# ModulePlatform.net
KiCad netlist of a schematic drawn in EAGLE
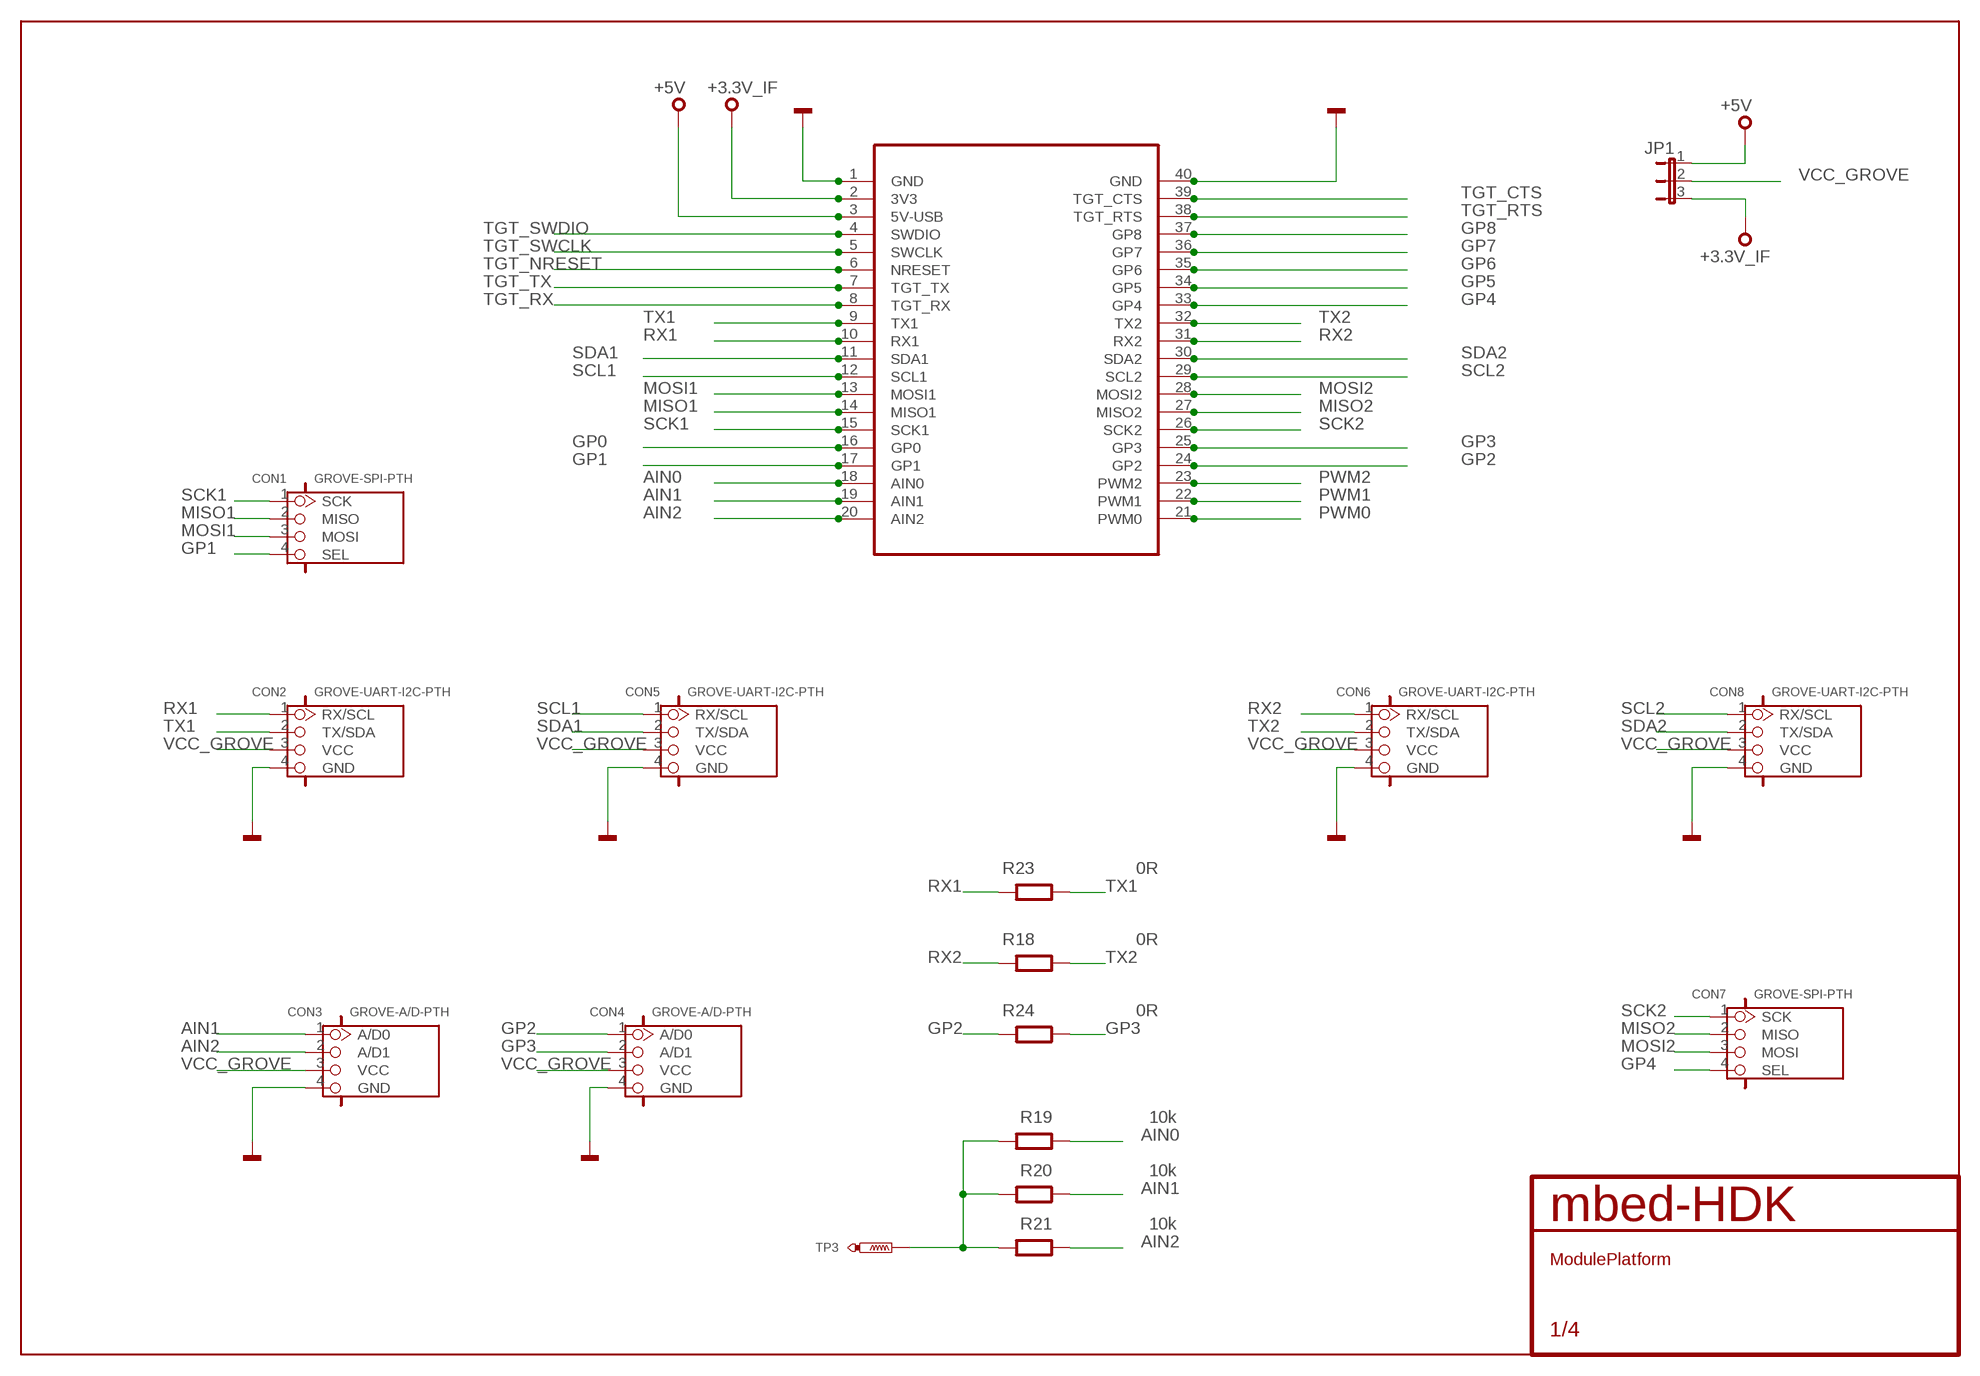
[diagram p0: schematic, sheet 1]
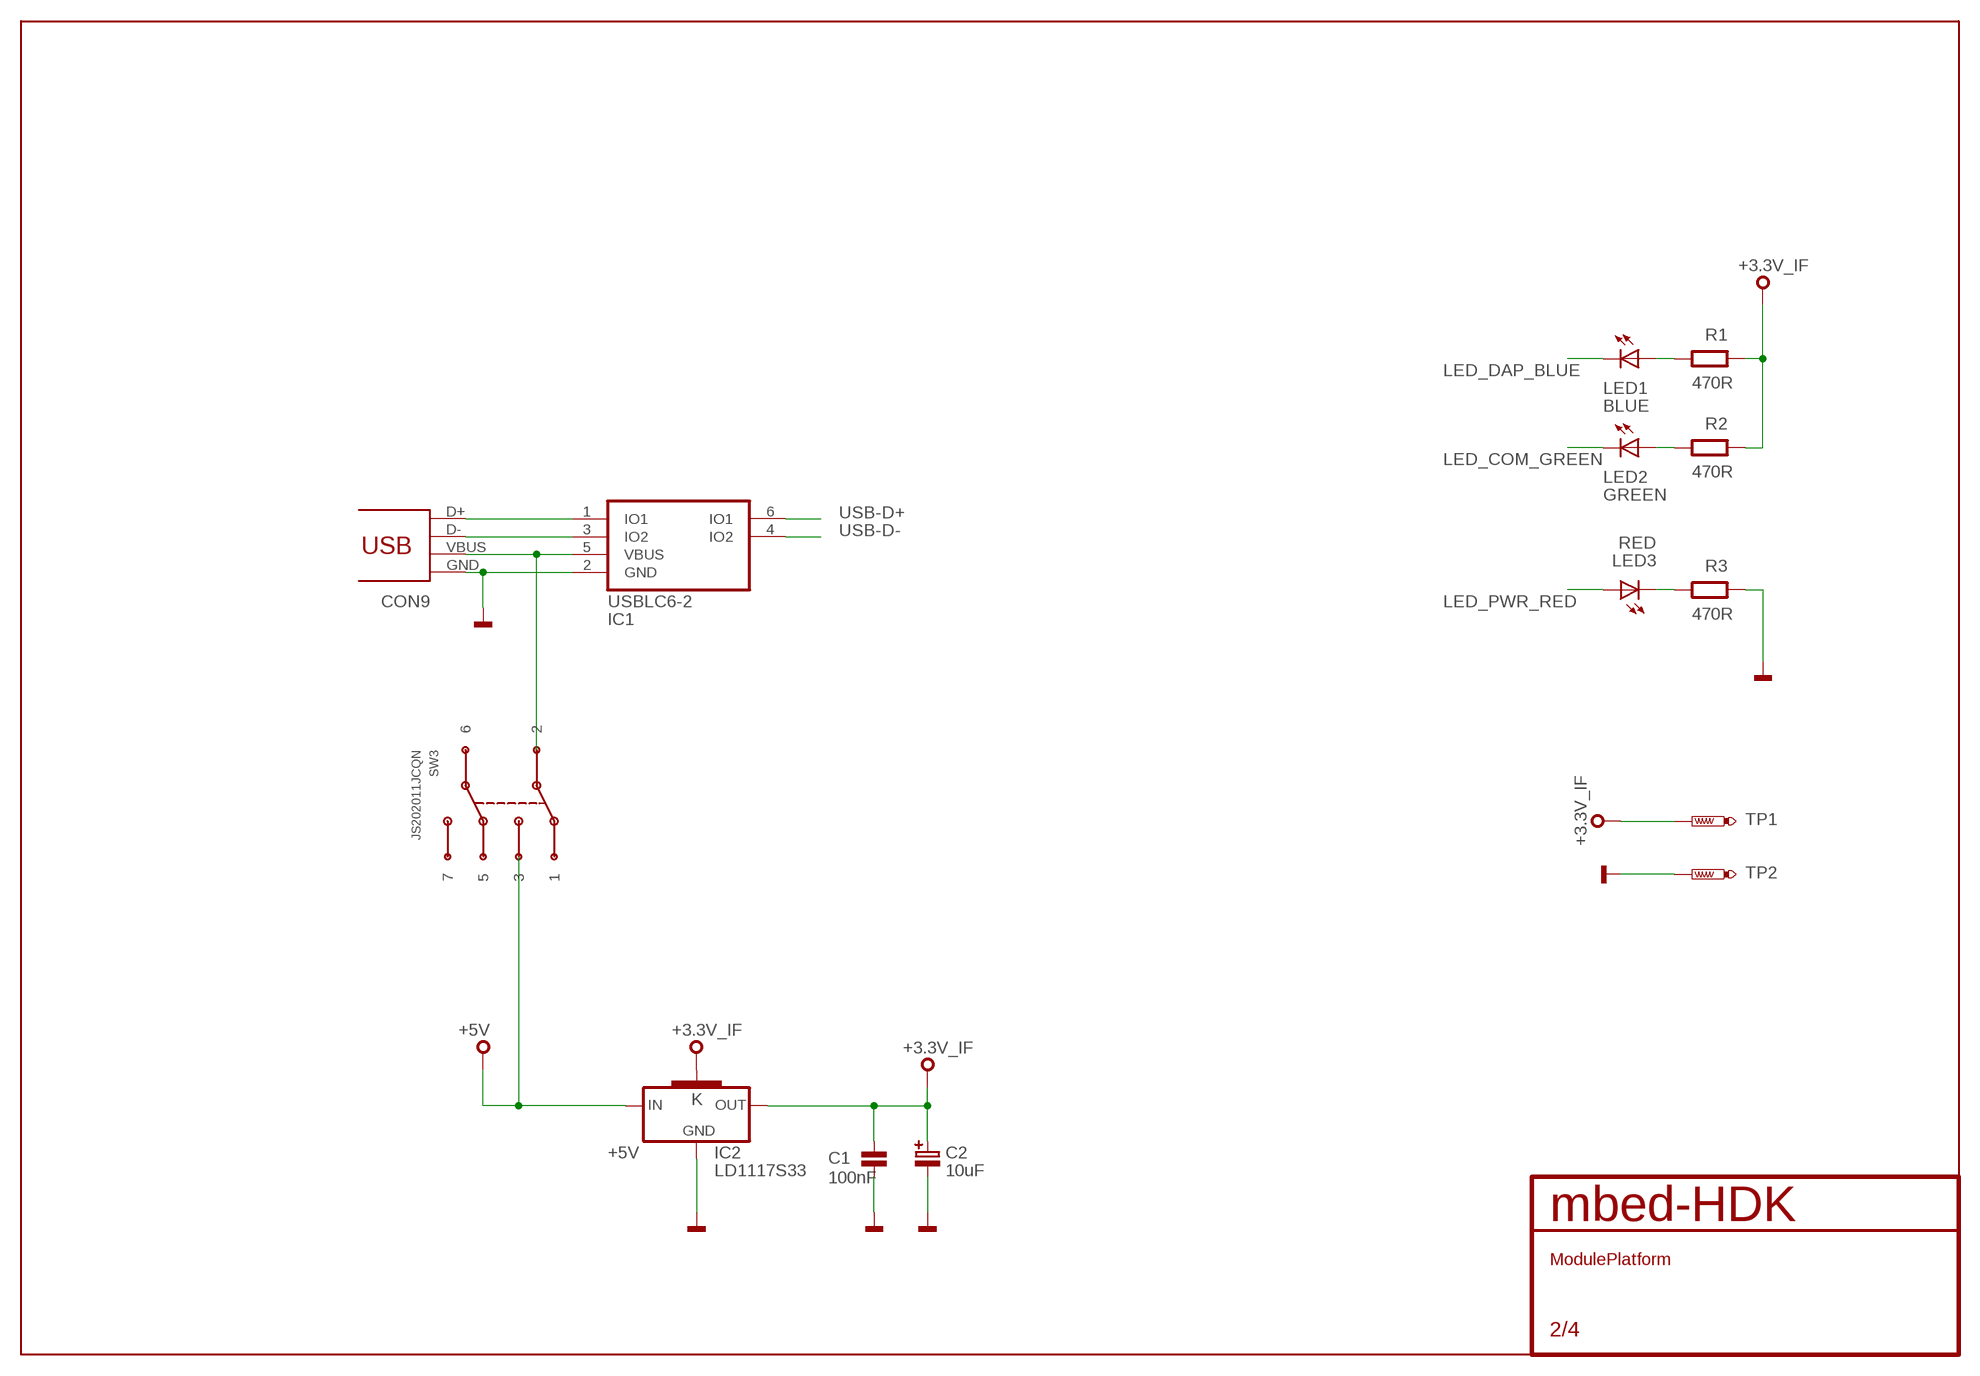
[diagram p1: schematic, sheet 2]
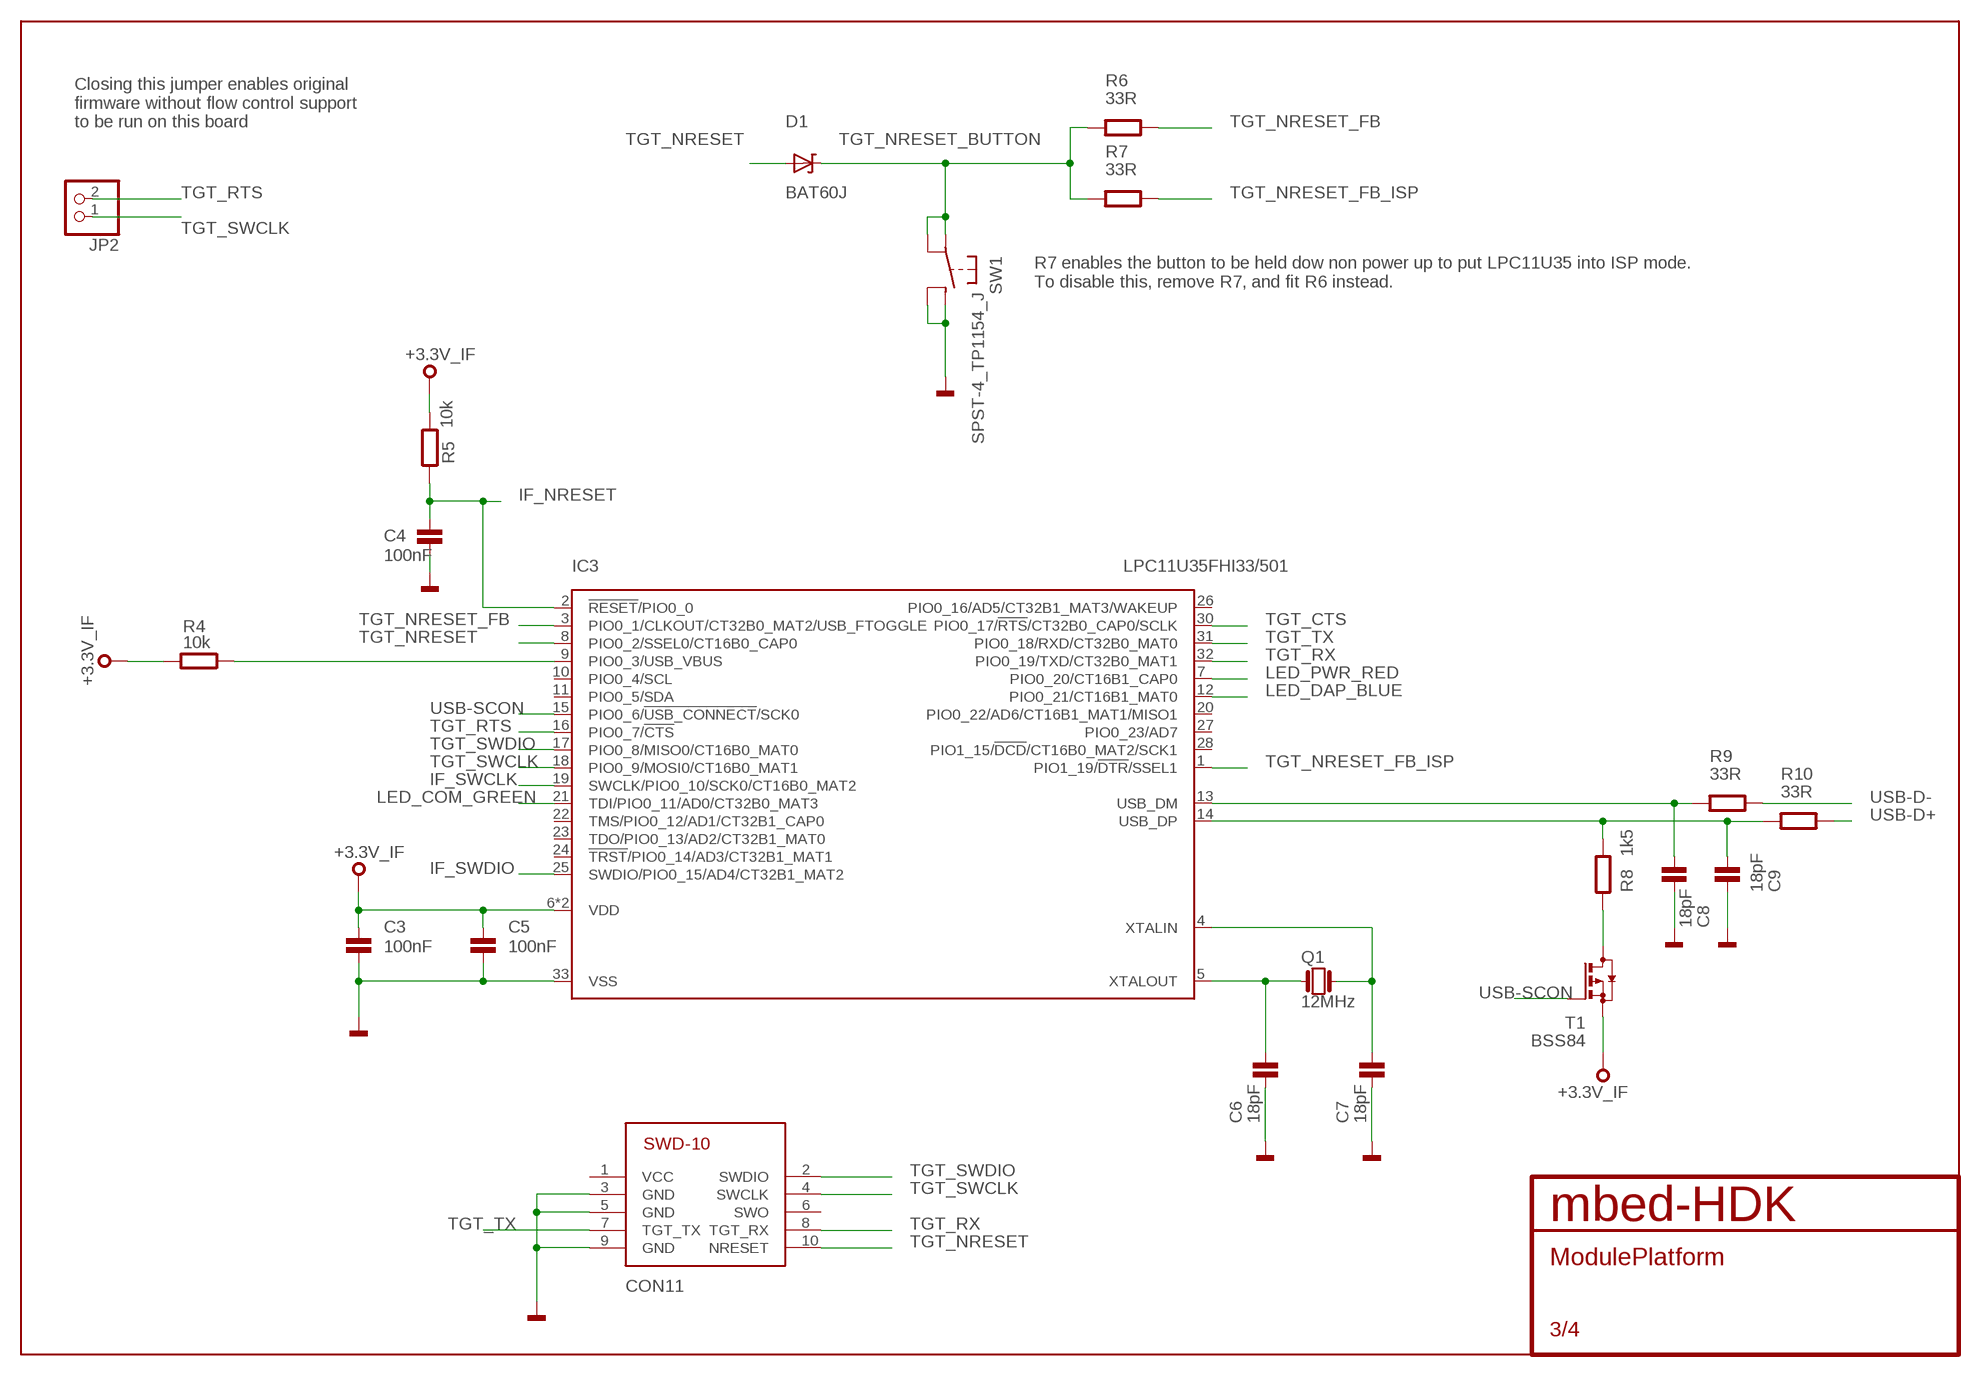
[diagram p2: schematic, sheet 3]
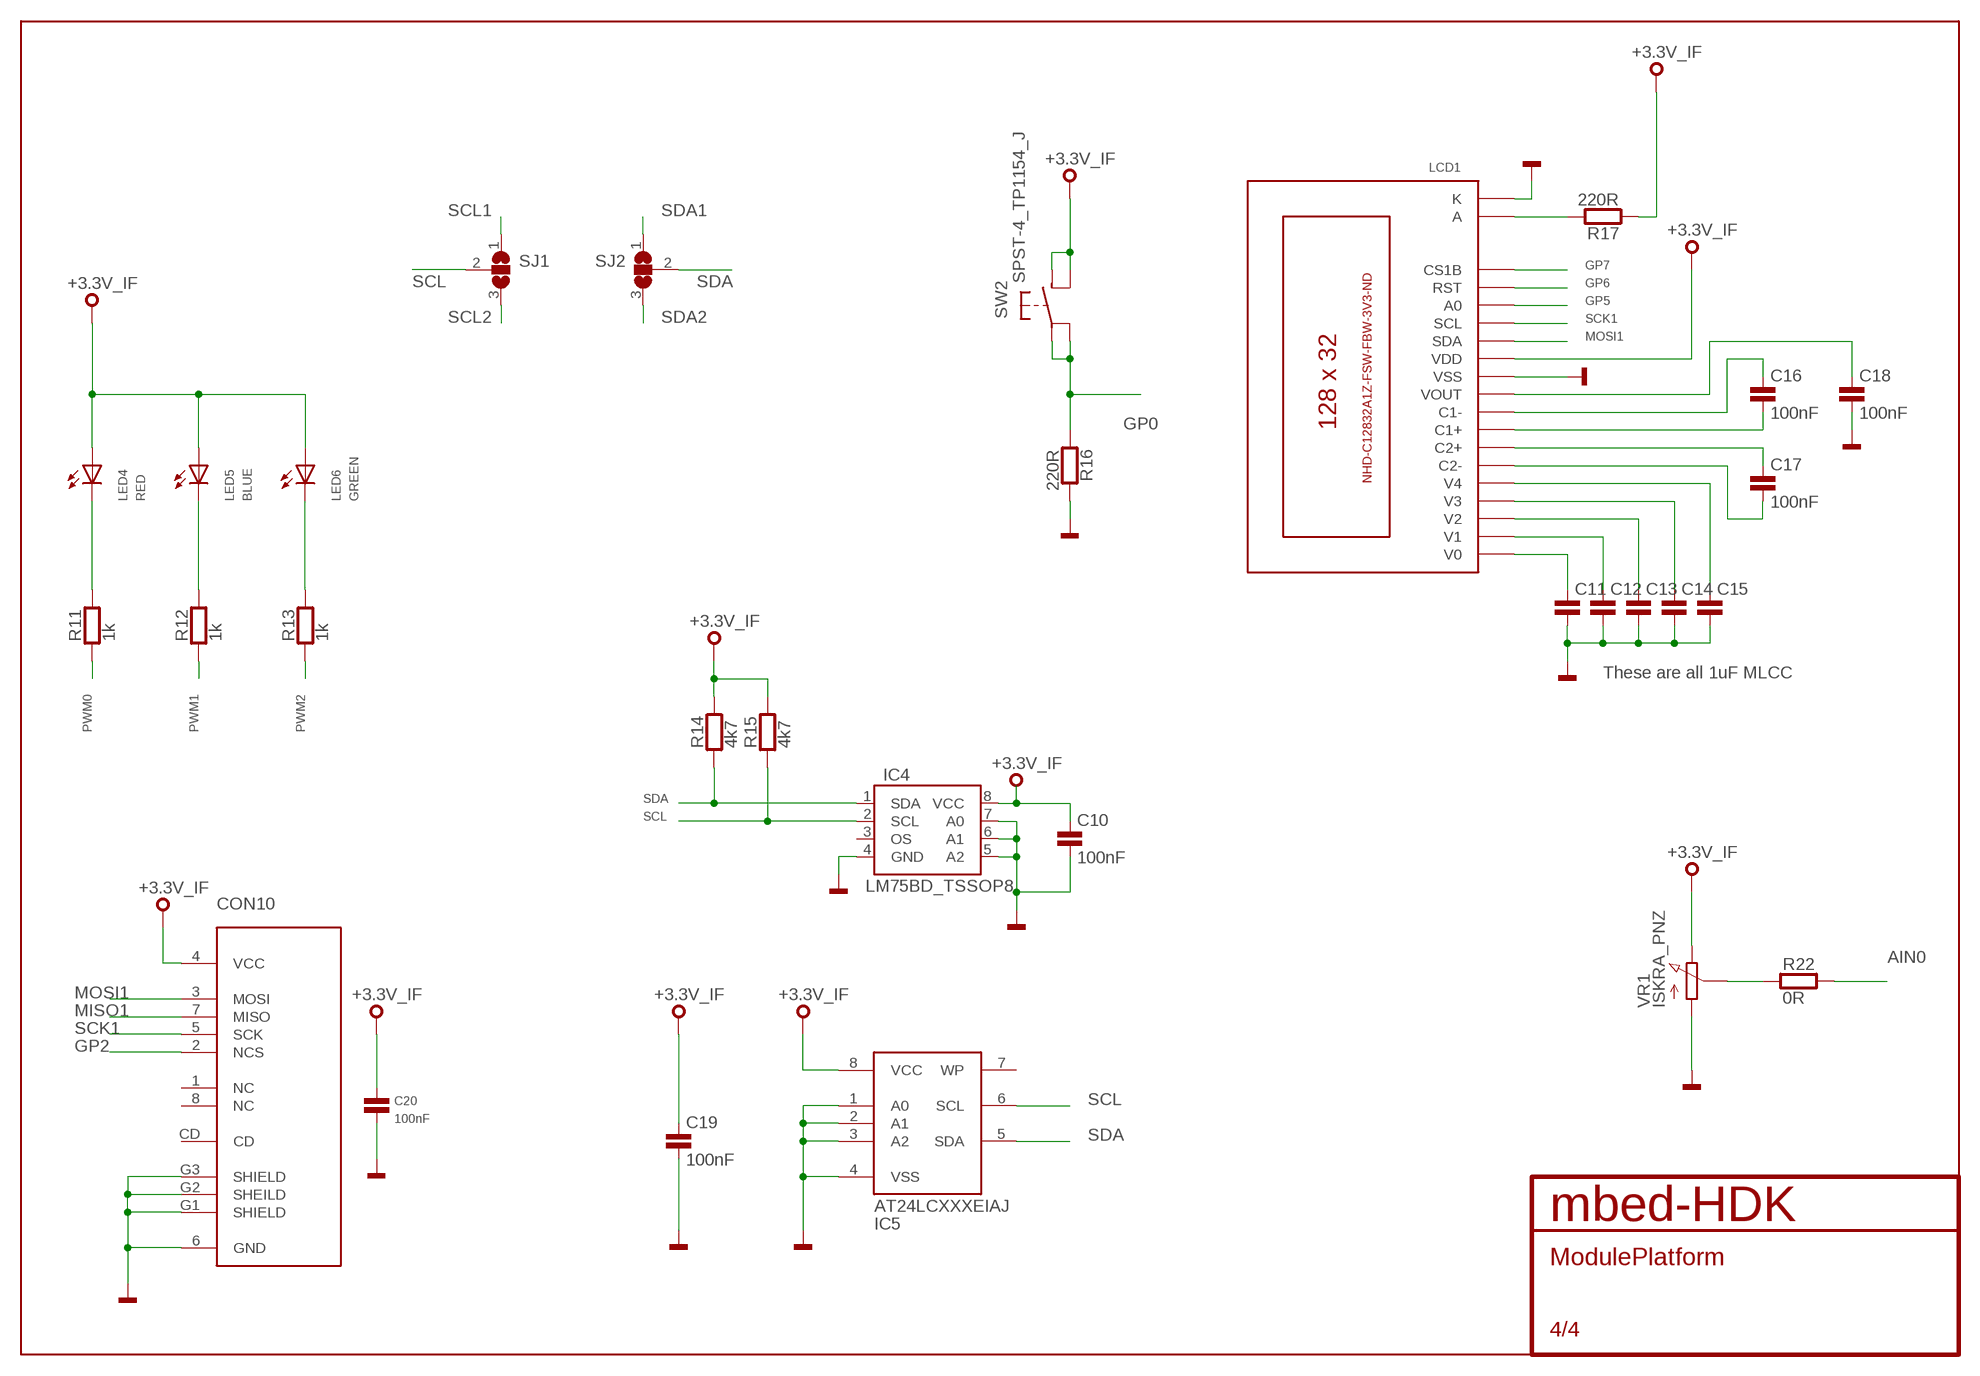
[diagram p3: schematic, sheet 4]

(export (version "E")
  (design (tool "Eeschema 10.0.6"))
  (components
    (comp (ref "CON1")
      (value "GROVE-SPI-PTH")
      (footprint "eagle-import:HW4-2.0")
      (libsource (lib "eagle-import") (part "GROVE-SPI-PTH"))
    )
    (comp (ref "CON2")
      (value "GROVE-UART-I2C-PTH")
      (footprint "eagle-import:HW4-2.0")
      (libsource (lib "eagle-import") (part "GROVE-UART-I2C-PTH"))
    )
    (comp (ref "CON3")
      (value "GROVE-A/D-PTH")
      (footprint "eagle-import:HW4-2.0")
      (libsource (lib "eagle-import") (part "GROVE-A/D-PTH"))
    )
    (comp (ref "CON4")
      (value "GROVE-A/D-PTH")
      (footprint "eagle-import:HW4-2.0")
      (libsource (lib "eagle-import") (part "GROVE-A/D-PTH"))
    )
    (comp (ref "CON5")
      (value "GROVE-UART-I2C-PTH")
      (footprint "eagle-import:HW4-2.0")
      (libsource (lib "eagle-import") (part "GROVE-UART-I2C-PTH"))
    )
    (comp (ref "CON6")
      (value "GROVE-UART-I2C-PTH")
      (footprint "eagle-import:HW4-2.0")
      (libsource (lib "eagle-import") (part "GROVE-UART-I2C-PTH"))
    )
    (comp (ref "CON7")
      (value "GROVE-SPI-PTH")
      (footprint "eagle-import:HW4-2.0")
      (libsource (lib "eagle-import") (part "GROVE-SPI-PTH"))
    )
    (comp (ref "CON8")
      (value "GROVE-UART-I2C-PTH")
      (footprint "eagle-import:HW4-2.0")
      (libsource (lib "eagle-import") (part "GROVE-UART-I2C-PTH"))
    )
    (comp (ref "JP1")
      (value "JP2E")
      (footprint "eagle-import:JP2")
      (libsource (lib "eagle-import") (part "JP2E"))
    )
    (comp (ref "R18")
      (value "0R")
      (footprint "eagle-import:0603@1")
      (libsource (lib "eagle-import") (part "R0603"))
    )
    (comp (ref "R19")
      (value "10k")
      (footprint "eagle-import:0603@1")
      (libsource (lib "eagle-import") (part "R0603"))
    )
    (comp (ref "R20")
      (value "10k")
      (footprint "eagle-import:0603@1")
      (libsource (lib "eagle-import") (part "R0603"))
    )
    (comp (ref "R21")
      (value "10k")
      (footprint "eagle-import:0603@1")
      (libsource (lib "eagle-import") (part "R0603"))
    )
    (comp (ref "R23")
      (value "0R")
      (footprint "eagle-import:0603@1")
      (libsource (lib "eagle-import") (part "R0603"))
    )
    (comp (ref "R24")
      (value "0R")
      (footprint "eagle-import:0603@1")
      (libsource (lib "eagle-import") (part "R0603"))
    )
    (comp (ref "SKT1")
      (value "MODULE_SOCKET")
      (footprint "eagle-import:MODULE_SOCKET")
      (libsource (lib "eagle-import") (part "MODULE_SOCKET"))
    )
    (comp (ref "TP3")
      (value "TEST-POINT-50R-PTH")
      (footprint "eagle-import:TP50-PTH")
      (libsource (lib "eagle-import") (part "TEST-POINT-50R-PTH"))
    )
    (comp (ref "C10")
      (value "100nF")
      (footprint "eagle-import:0603")
      (libsource (lib "eagle-import") (part "mbed-rlcq_C0603"))
    )
    (comp (ref "C11")
      (value "100nF")
      (footprint "eagle-import:0603")
      (libsource (lib "eagle-import") (part "mbed-rlcq_C0603"))
    )
    (comp (ref "C12")
      (value "100nF")
      (footprint "eagle-import:0603")
      (libsource (lib "eagle-import") (part "mbed-rlcq_C0603"))
    )
    (comp (ref "C13")
      (value "100nF")
      (footprint "eagle-import:0603")
      (libsource (lib "eagle-import") (part "mbed-rlcq_C0603"))
    )
    (comp (ref "C14")
      (value "100nF")
      (footprint "eagle-import:0603")
      (libsource (lib "eagle-import") (part "mbed-rlcq_C0603"))
    )
    (comp (ref "C15")
      (value "100nF")
      (footprint "eagle-import:0603")
      (libsource (lib "eagle-import") (part "mbed-rlcq_C0603"))
    )
    (comp (ref "C16")
      (value "100nF")
      (footprint "eagle-import:0603")
      (libsource (lib "eagle-import") (part "mbed-rlcq_C0603"))
    )
    (comp (ref "C17")
      (value "100nF")
      (footprint "eagle-import:0603")
      (libsource (lib "eagle-import") (part "mbed-rlcq_C0603"))
    )
    (comp (ref "C18")
      (value "100nF")
      (footprint "eagle-import:0603")
      (libsource (lib "eagle-import") (part "mbed-rlcq_C0603"))
    )
    (comp (ref "C19")
      (value "100nF")
      (footprint "eagle-import:0603")
      (libsource (lib "eagle-import") (part "mbed-rlcq_C0603"))
    )
    (comp (ref "C20")
      (value "100nF")
      (footprint "eagle-import:0603")
      (libsource (lib "eagle-import") (part "C0603"))
    )
    (comp (ref "CON10")
      (value "MICRO-SD")
      (footprint "eagle-import:AMPHENOL-101-00660-68-6")
      (libsource (lib "eagle-import") (part "MICRO-SD"))
    )
    (comp (ref "IC4")
      (value "LM75BD_TSSOP8")
      (footprint "eagle-import:TSSOP8")
      (libsource (lib "eagle-import") (part "LM75BD_TSSOP8"))
    )
    (comp (ref "IC5")
      (value "AT24LCXXXEIAJ")
      (footprint "eagle-import:SO08-EIAJ")
      (libsource (lib "eagle-import") (part "AT24LCXXXEIAJ"))
    )
    (comp (ref "LCD1")
      (value "C12832A1Z")
      (footprint "eagle-import:C12832A1Z")
      (libsource (lib "eagle-import") (part "C12832A1Z"))
    )
    (comp (ref "LED4")
      (value "RED")
      (footprint "eagle-import:CHIPLED_0603")
      (libsource (lib "eagle-import") (part "LED0603"))
    )
    (comp (ref "LED5")
      (value "BLUE")
      (footprint "eagle-import:CHIPLED_0603")
      (libsource (lib "eagle-import") (part "LED0603"))
    )
    (comp (ref "LED6")
      (value "GREEN")
      (footprint "eagle-import:CHIPLED_0603")
      (libsource (lib "eagle-import") (part "LED0603"))
    )
    (comp (ref "R11")
      (value "1k")
      (footprint "eagle-import:0603")
      (libsource (lib "eagle-import") (part "mbed-rlcq_R0603"))
    )
    (comp (ref "R12")
      (value "1k")
      (footprint "eagle-import:0603")
      (libsource (lib "eagle-import") (part "mbed-rlcq_R0603"))
    )
    (comp (ref "R13")
      (value "1k")
      (footprint "eagle-import:0603")
      (libsource (lib "eagle-import") (part "mbed-rlcq_R0603"))
    )
    (comp (ref "R14")
      (value "4k7")
      (footprint "eagle-import:0603")
      (libsource (lib "eagle-import") (part "mbed-rlcq_R0603"))
    )
    (comp (ref "R15")
      (value "4k7")
      (footprint "eagle-import:0603")
      (libsource (lib "eagle-import") (part "mbed-rlcq_R0603"))
    )
    (comp (ref "R16")
      (value "220R")
      (footprint "eagle-import:0603")
      (libsource (lib "eagle-import") (part "mbed-rlcq_R0603"))
    )
    (comp (ref "R17")
      (value "220R")
      (footprint "eagle-import:0603")
      (libsource (lib "eagle-import") (part "mbed-rlcq_R0603"))
    )
    (comp (ref "R22")
      (value "0R")
      (footprint "eagle-import:0603")
      (libsource (lib "eagle-import") (part "mbed-rlcq_R0603"))
    )
    (comp (ref "SJ1")
      (value "SJ2W")
      (footprint "eagle-import:SJ_2")
      (libsource (lib "eagle-import") (part "SJ2W"))
    )
    (comp (ref "SJ2")
      (value "SJ2W")
      (footprint "eagle-import:SJ_2")
      (libsource (lib "eagle-import") (part "SJ2W"))
    )
    (comp (ref "SW2")
      (value "SPST-4_TP1154_J")
      (footprint "eagle-import:TP-1154X")
      (libsource (lib "eagle-import") (part "SPST-4_TP1154_J"))
    )
    (comp (ref "VR1")
      (value "ISKRA_PNZ")
      (footprint "eagle-import:CA14V")
      (libsource (lib "eagle-import") (part "ISKRA_PNZ"))
    )
    (comp (ref "C1")
      (value "100nF")
      (footprint "eagle-import:0603")
      (libsource (lib "eagle-import") (part "C0603"))
    )
    (comp (ref "C2")
      (value "10uF")
      (footprint "eagle-import:SMC_B")
      (libsource (lib "eagle-import") (part "C-POLB"))
    )
    (comp (ref "CON9")
      (value "USB_MICROB")
      (footprint "eagle-import:MOLEX-47364-0001")
      (libsource (lib "eagle-import") (part "USB_MICROB"))
    )
    (comp (ref "IC1")
      (value "USBLC6-2SC6")
      (footprint "eagle-import:SOT23-6L")
      (libsource (lib "eagle-import") (part "USBLC6-2SC6"))
    )
    (comp (ref "IC2")
      (value "LD1117S33")
      (footprint "eagle-import:SOT223")
      (libsource (lib "eagle-import") (part "LD1117S33"))
    )
    (comp (ref "LED1")
      (value "BLUE")
      (footprint "eagle-import:CHIPLED_0603")
      (libsource (lib "eagle-import") (part "LED0603"))
    )
    (comp (ref "LED2")
      (value "GREEN")
      (footprint "eagle-import:CHIPLED_0603")
      (libsource (lib "eagle-import") (part "LED0603"))
    )
    (comp (ref "LED3")
      (value "RED")
      (footprint "eagle-import:CHIPLED_0603")
      (libsource (lib "eagle-import") (part "LED0603"))
    )
    (comp (ref "R1")
      (value "470R")
      (footprint "eagle-import:0603@1")
      (libsource (lib "eagle-import") (part "R0603"))
    )
    (comp (ref "R2")
      (value "470R")
      (footprint "eagle-import:0603@1")
      (libsource (lib "eagle-import") (part "R0603"))
    )
    (comp (ref "R3")
      (value "470R")
      (footprint "eagle-import:0603@1")
      (libsource (lib "eagle-import") (part "R0603"))
    )
    (comp (ref "SW3")
      (value "JS202011JCQN")
      (footprint "eagle-import:JS202011JCQN")
      (fields (field (name "MF") "C&K Components"))
      (libsource (lib "eagle-import") (part "JS202011JCQN"))
    )
    (comp (ref "TP1")
      (value "TEST-POINT-50R-PTH")
      (footprint "eagle-import:TP50-PTH")
      (libsource (lib "eagle-import") (part "TEST-POINT-50R-PTH"))
    )
    (comp (ref "TP2")
      (value "TEST-POINT-50R-PTH")
      (footprint "eagle-import:TP50-PTH")
      (libsource (lib "eagle-import") (part "TEST-POINT-50R-PTH"))
    )
    (comp (ref "C3")
      (value "100nF")
      (footprint "eagle-import:0603")
      (libsource (lib "eagle-import") (part "C0603"))
    )
    (comp (ref "C4")
      (value "100nF")
      (footprint "eagle-import:0603")
      (libsource (lib "eagle-import") (part "C0603"))
    )
    (comp (ref "C5")
      (value "100nF")
      (footprint "eagle-import:0603")
      (libsource (lib "eagle-import") (part "C0603"))
    )
    (comp (ref "C6")
      (value "18pF")
      (footprint "eagle-import:0603")
      (libsource (lib "eagle-import") (part "C0603"))
    )
    (comp (ref "C7")
      (value "18pF")
      (footprint "eagle-import:0603")
      (libsource (lib "eagle-import") (part "C0603"))
    )
    (comp (ref "C8")
      (value "18pF")
      (footprint "eagle-import:0603")
      (libsource (lib "eagle-import") (part "C0603"))
    )
    (comp (ref "C9")
      (value "18pF")
      (footprint "eagle-import:0603")
      (libsource (lib "eagle-import") (part "C0603"))
    )
    (comp (ref "CON11")
      (value "SWD-10/TC2050_SMD")
      (footprint "eagle-import:FTSH-105-02")
      (libsource (lib "eagle-import") (part "SWD-10/TC2050_SMD"))
    )
    (comp (ref "D1")
      (value "BAT60J")
      (footprint "eagle-import:BAT60A")
      (libsource (lib "eagle-import") (part "BAT60A"))
    )
    (comp (ref "IC3")
      (value "LPC11U35FHI33/501")
      (footprint "eagle-import:SOT617-3")
      (libsource (lib "eagle-import") (part "LPC11U35FHI33/501"))
    )
    (comp (ref "JP2")
      (value "PINHD-1X2")
      (footprint "eagle-import:1X02")
      (libsource (lib "eagle-import") (part "PINHD-1X2"))
    )
    (comp (ref "Q1")
      (value "12MHz")
      (footprint "eagle-import:3.2X.2.5")
      (libsource (lib "eagle-import") (part "Q_3.2X2.5"))
    )
    (comp (ref "R4")
      (value "10k")
      (footprint "eagle-import:0603@1")
      (libsource (lib "eagle-import") (part "R0603"))
    )
    (comp (ref "R5")
      (value "10k")
      (footprint "eagle-import:0603@1")
      (libsource (lib "eagle-import") (part "R0603"))
    )
    (comp (ref "R6")
      (value "33R")
      (footprint "eagle-import:0603@1")
      (libsource (lib "eagle-import") (part "R0603"))
    )
    (comp (ref "R7")
      (value "33R")
      (footprint "eagle-import:0603@1")
      (libsource (lib "eagle-import") (part "R0603"))
    )
    (comp (ref "R8")
      (value "1k5")
      (footprint "eagle-import:0603@1")
      (libsource (lib "eagle-import") (part "R0603"))
    )
    (comp (ref "R9")
      (value "33R")
      (footprint "eagle-import:0603@1")
      (libsource (lib "eagle-import") (part "R0603"))
    )
    (comp (ref "R10")
      (value "33R")
      (footprint "eagle-import:0603@1")
      (libsource (lib "eagle-import") (part "R0603"))
    )
    (comp (ref "SW1")
      (value "SPST-4_TP1154_J")
      (footprint "eagle-import:TP-1154X")
      (libsource (lib "eagle-import") (part "SPST-4_TP1154_J"))
    )
    (comp (ref "T1")
      (value "BSS84")
      (footprint "eagle-import:SOT23")
      (libsource (lib "eagle-import") (part "BSS84"))
    )
  )
  (nets
    (net (code "1") (name "+3.3V_IF") (class "Default")
      (node (ref "C1") (pin "1") (pinfunction "P$1_1") (pintype "passive"))
      (node (ref "C10") (pin "1") (pinfunction "P$1_1") (pintype "passive"))
      (node (ref "C19") (pin "1") (pinfunction "P$1_1") (pintype "passive"))
      (node (ref "C2") (pin "+") (pinfunction "+_+") (pintype "passive"))
      (node (ref "C20") (pin "1") (pinfunction "P$1_1") (pintype "passive"))
      (node (ref "C3") (pin "1") (pinfunction "P$1_1") (pintype "passive"))
      (node (ref "C5") (pin "1") (pinfunction "P$1_1") (pintype "passive"))
      (node (ref "CON10") (pin "4") (pinfunction "VCC_4") (pintype "bidirectional"))
      (node (ref "IC2") (pin "2") (pinfunction "OUT_2") (pintype "passive"))
      (node (ref "IC2") (pin "4") (pinfunction "K_4") (pintype "passive"))
      (node (ref "IC3") (pin "29") (pinfunction "VDD_29") (pintype "passive"))
      (node (ref "IC3") (pin "6") (pinfunction "VDD_6") (pintype "passive"))
      (node (ref "IC4") (pin "8") (pinfunction "VCC_8") (pintype "bidirectional"))
      (node (ref "IC5") (pin "8") (pinfunction "VCC_8") (pintype "power_in"))
      (node (ref "JP1") (pin "3") (pinfunction "3_3") (pintype "passive"))
      (node (ref "LCD1") (pin "P$12") (pinfunction "VDD_P$12") (pintype "bidirectional"))
      (node (ref "LED4") (pin "A") (pinfunction "A_A") (pintype "passive"))
      (node (ref "LED5") (pin "A") (pinfunction "A_A") (pintype "passive"))
      (node (ref "LED6") (pin "A") (pinfunction "A_A") (pintype "passive"))
      (node (ref "R1") (pin "1") (pinfunction "P$1_1") (pintype "passive"))
      (node (ref "R14") (pin "2") (pinfunction "P$2_2") (pintype "passive"))
      (node (ref "R15") (pin "2") (pinfunction "P$2_2") (pintype "passive"))
      (node (ref "R17") (pin "1") (pinfunction "P$1_1") (pintype "passive"))
      (node (ref "R2") (pin "1") (pinfunction "P$1_1") (pintype "passive"))
      (node (ref "R4") (pin "2") (pinfunction "P$2_2") (pintype "passive"))
      (node (ref "R5") (pin "2") (pinfunction "P$2_2") (pintype "passive"))
      (node (ref "SKT1") (pin "2") (pinfunction "3V3_2") (pintype "bidirectional"))
      (node (ref "SKT1") (pin "P$42") (pinfunction "P$42_P$42") (pintype "bidirectional"))
      (node (ref "SW2") (pin "B1") (pinfunction "B1_B1") (pintype "passive"))
      (node (ref "SW2") (pin "B2") (pinfunction "B2_B2") (pintype "passive"))
      (node (ref "T1") (pin "2") (pinfunction "S_2") (pintype "passive"))
      (node (ref "TP1") (pin "TP") (pinfunction "TP_TP") (pintype "input"))
      (node (ref "VR1") (pin "P$3") (pinfunction "E_P$3") (pintype "passive"))
    )
    (net (code "2") (name "+5V") (class "Default")
      (node (ref "IC2") (pin "3") (pinfunction "IN_3") (pintype "input"))
      (node (ref "JP1") (pin "1") (pinfunction "1_1") (pintype "passive"))
      (node (ref "SKT1") (pin "3") (pinfunction "5V-USB_3") (pintype "bidirectional"))
      (node (ref "SKT1") (pin "P$43") (pinfunction "P$43_P$43") (pintype "bidirectional"))
      (node (ref "SW3") (pin "3") (pinfunction "3_3") (pintype "bidirectional"))
    )
    (net (code "3") (name "AIN0") (class "Default")
      (node (ref "R19") (pin "1") (pinfunction "P$1_1") (pintype "passive"))
      (node (ref "R22") (pin "2") (pinfunction "P$2_2") (pintype "passive"))
      (node (ref "SKT1") (pin "18") (pinfunction "AIN0_18") (pintype "bidirectional"))
      (node (ref "SKT1") (pin "P$58") (pinfunction "P$58_P$58") (pintype "bidirectional"))
    )
    (net (code "4") (name "AIN1") (class "Default")
      (node (ref "CON3") (pin "1") (pinfunction "A/D0_1") (pintype "bidirectional"))
      (node (ref "R20") (pin "1") (pinfunction "P$1_1") (pintype "passive"))
      (node (ref "SKT1") (pin "19") (pinfunction "AIN1_19") (pintype "bidirectional"))
      (node (ref "SKT1") (pin "P$59") (pinfunction "P$59_P$59") (pintype "bidirectional"))
    )
    (net (code "5") (name "AIN2") (class "Default")
      (node (ref "CON3") (pin "2") (pinfunction "A/D1_2") (pintype "bidirectional"))
      (node (ref "R21") (pin "1") (pinfunction "P$1_1") (pintype "passive"))
      (node (ref "SKT1") (pin "20") (pinfunction "AIN2_20") (pintype "bidirectional"))
      (node (ref "SKT1") (pin "P$60") (pinfunction "P$60_P$60") (pintype "bidirectional"))
    )
    (net (code "6") (name "GND") (class "Default")
      (node (ref "C1") (pin "2") (pinfunction "P$2_2") (pintype "passive"))
      (node (ref "C10") (pin "2") (pinfunction "P$2_2") (pintype "passive"))
      (node (ref "C11") (pin "2") (pinfunction "P$2_2") (pintype "passive"))
      (node (ref "C12") (pin "2") (pinfunction "P$2_2") (pintype "passive"))
      (node (ref "C13") (pin "2") (pinfunction "P$2_2") (pintype "passive"))
      (node (ref "C14") (pin "2") (pinfunction "P$2_2") (pintype "passive"))
      (node (ref "C15") (pin "2") (pinfunction "P$2_2") (pintype "passive"))
      (node (ref "C18") (pin "2") (pinfunction "P$2_2") (pintype "passive"))
      (node (ref "C19") (pin "2") (pinfunction "P$2_2") (pintype "passive"))
      (node (ref "C2") (pin "-") (pinfunction "-_-") (pintype "passive"))
      (node (ref "C20") (pin "2") (pinfunction "P$2_2") (pintype "passive"))
      (node (ref "C3") (pin "2") (pinfunction "P$2_2") (pintype "passive"))
      (node (ref "C4") (pin "2") (pinfunction "P$2_2") (pintype "passive"))
      (node (ref "C5") (pin "2") (pinfunction "P$2_2") (pintype "passive"))
      (node (ref "C6") (pin "2") (pinfunction "P$2_2") (pintype "passive"))
      (node (ref "C7") (pin "2") (pinfunction "P$2_2") (pintype "passive"))
      (node (ref "C8") (pin "2") (pinfunction "P$2_2") (pintype "passive"))
      (node (ref "C9") (pin "2") (pinfunction "P$2_2") (pintype "passive"))
      (node (ref "CON10") (pin "6") (pinfunction "GND_6") (pintype "bidirectional"))
      (node (ref "CON10") (pin "G1") (pinfunction "SHIELD_G1") (pintype "bidirectional"))
      (node (ref "CON10") (pin "G2") (pinfunction "SHEILD_G2") (pintype "bidirectional"))
      (node (ref "CON10") (pin "G3") (pinfunction "SHIELD_G3") (pintype "bidirectional"))
      (node (ref "CON11") (pin "3") (pinfunction "GND_3") (pintype "bidirectional"))
      (node (ref "CON11") (pin "5") (pinfunction "GND_5") (pintype "bidirectional"))
      (node (ref "CON11") (pin "9") (pinfunction "GND_9") (pintype "bidirectional"))
      (node (ref "CON2") (pin "4") (pinfunction "GND_4") (pintype "bidirectional"))
      (node (ref "CON3") (pin "4") (pinfunction "GND_4") (pintype "bidirectional"))
      (node (ref "CON4") (pin "4") (pinfunction "GND_4") (pintype "bidirectional"))
      (node (ref "CON5") (pin "4") (pinfunction "GND_4") (pintype "bidirectional"))
      (node (ref "CON6") (pin "4") (pinfunction "GND_4") (pintype "bidirectional"))
      (node (ref "CON8") (pin "4") (pinfunction "GND_4") (pintype "bidirectional"))
      (node (ref "CON9") (pin "GND") (pinfunction "GND_GND") (pintype "bidirectional"))
      (node (ref "IC1") (pin "2") (pinfunction "GND_2") (pintype "bidirectional"))
      (node (ref "IC2") (pin "1") (pinfunction "GND_1") (pintype "input"))
      (node (ref "IC3") (pin "33") (pinfunction "VSS_33") (pintype "passive"))
      (node (ref "IC4") (pin "4") (pinfunction "GND_4") (pintype "bidirectional"))
      (node (ref "IC4") (pin "5") (pinfunction "A2_5") (pintype "bidirectional"))
      (node (ref "IC4") (pin "6") (pinfunction "A1_6") (pintype "bidirectional"))
      (node (ref "IC4") (pin "7") (pinfunction "A0_7") (pintype "bidirectional"))
      (node (ref "IC5") (pin "1") (pinfunction "A0_1") (pintype "bidirectional"))
      (node (ref "IC5") (pin "2") (pinfunction "A1_2") (pintype "bidirectional"))
      (node (ref "IC5") (pin "3") (pinfunction "A2_3") (pintype "bidirectional"))
      (node (ref "IC5") (pin "4") (pinfunction "VSS_4") (pintype "power_in"))
      (node (ref "LCD1") (pin "K") (pinfunction "K_K") (pintype "bidirectional"))
      (node (ref "LCD1") (pin "P$11") (pinfunction "VSS_P$11") (pintype "bidirectional"))
      (node (ref "R16") (pin "2") (pinfunction "P$2_2") (pintype "passive"))
      (node (ref "R3") (pin "1") (pinfunction "P$1_1") (pintype "passive"))
      (node (ref "SKT1") (pin "1") (pinfunction "GND_1") (pintype "bidirectional"))
      (node (ref "SKT1") (pin "40") (pinfunction "GND_40") (pintype "bidirectional"))
      (node (ref "SKT1") (pin "P$41") (pinfunction "P$41_P$41") (pintype "bidirectional"))
      (node (ref "SKT1") (pin "P$80") (pinfunction "P$80_P$80") (pintype "bidirectional"))
      (node (ref "SW1") (pin "B1") (pinfunction "B1_B1") (pintype "passive"))
      (node (ref "SW1") (pin "B2") (pinfunction "B2_B2") (pintype "passive"))
      (node (ref "TP2") (pin "TP") (pinfunction "TP_TP") (pintype "input"))
      (node (ref "VR1") (pin "P$1") (pinfunction "A_P$1") (pintype "passive"))
    )
    (net (code "7") (name "GP0") (class "Default")
      (node (ref "R16") (pin "1") (pinfunction "P$1_1") (pintype "passive"))
      (node (ref "SKT1") (pin "16") (pinfunction "GP0_16") (pintype "bidirectional"))
      (node (ref "SKT1") (pin "P$56") (pinfunction "P$56_P$56") (pintype "bidirectional"))
      (node (ref "SW2") (pin "A1") (pinfunction "A1_A1") (pintype "passive"))
      (node (ref "SW2") (pin "A2") (pinfunction "A2_A2") (pintype "passive"))
    )
    (net (code "8") (name "GP1") (class "Default")
      (node (ref "CON1") (pin "4") (pinfunction "SEL_4") (pintype "bidirectional"))
      (node (ref "SKT1") (pin "17") (pinfunction "GP1_17") (pintype "bidirectional"))
      (node (ref "SKT1") (pin "P$57") (pinfunction "P$57_P$57") (pintype "bidirectional"))
    )
    (net (code "9") (name "GP2") (class "Default")
      (node (ref "CON10") (pin "2") (pinfunction "NCS_2") (pintype "bidirectional"))
      (node (ref "CON4") (pin "1") (pinfunction "A/D0_1") (pintype "bidirectional"))
      (node (ref "R24") (pin "2") (pinfunction "P$2_2") (pintype "passive"))
      (node (ref "SKT1") (pin "24") (pinfunction "GP2_24") (pintype "bidirectional"))
      (node (ref "SKT1") (pin "P$64") (pinfunction "P$64_P$64") (pintype "bidirectional"))
    )
    (net (code "10") (name "GP3") (class "Default")
      (node (ref "CON4") (pin "2") (pinfunction "A/D1_2") (pintype "bidirectional"))
      (node (ref "R24") (pin "1") (pinfunction "P$1_1") (pintype "passive"))
      (node (ref "SKT1") (pin "25") (pinfunction "GP3_25") (pintype "bidirectional"))
      (node (ref "SKT1") (pin "P$65") (pinfunction "P$65_P$65") (pintype "bidirectional"))
    )
    (net (code "11") (name "GP4") (class "Default")
      (node (ref "CON7") (pin "4") (pinfunction "SEL_4") (pintype "bidirectional"))
      (node (ref "SKT1") (pin "33") (pinfunction "GP4_33") (pintype "bidirectional"))
      (node (ref "SKT1") (pin "P$73") (pinfunction "P$73_P$73") (pintype "bidirectional"))
    )
    (net (code "12") (name "GP5") (class "Default")
      (node (ref "LCD1") (pin "P$15") (pinfunction "A0_P$15") (pintype "bidirectional"))
      (node (ref "SKT1") (pin "34") (pinfunction "GP5_34") (pintype "bidirectional"))
      (node (ref "SKT1") (pin "P$74") (pinfunction "P$74_P$74") (pintype "bidirectional"))
    )
    (net (code "13") (name "GP6") (class "Default")
      (node (ref "LCD1") (pin "P$16") (pinfunction "RST_P$16") (pintype "bidirectional"))
      (node (ref "SKT1") (pin "35") (pinfunction "GP6_35") (pintype "bidirectional"))
      (node (ref "SKT1") (pin "P$75") (pinfunction "P$75_P$75") (pintype "bidirectional"))
    )
    (net (code "14") (name "GP7") (class "Default")
      (node (ref "LCD1") (pin "P$17") (pinfunction "CS1B_P$17") (pintype "bidirectional"))
      (node (ref "SKT1") (pin "36") (pinfunction "GP7_36") (pintype "bidirectional"))
      (node (ref "SKT1") (pin "P$76") (pinfunction "P$76_P$76") (pintype "bidirectional"))
    )
    (net (code "15") (name "GP8") (class "Default")
      (node (ref "SKT1") (pin "37") (pinfunction "GP8_37") (pintype "bidirectional"))
      (node (ref "SKT1") (pin "P$77") (pinfunction "P$77_P$77") (pintype "bidirectional"))
    )
    (net (code "16") (name "IF_NRESET") (class "Default")
      (node (ref "C4") (pin "1") (pinfunction "P$1_1") (pintype "passive"))
      (node (ref "IC3") (pin "2") (pinfunction "~{RESET}/PIO0_0_2") (pintype "bidirectional"))
      (node (ref "R5") (pin "1") (pinfunction "P$1_1") (pintype "passive"))
    )
    (net (code "17") (name "IF_SWCLK") (class "Default")
      (node (ref "IC3") (pin "19") (pinfunction "SWCLK/PIO0_10/SCK0/CT16B0_MAT2_19") (pintype "bidirectional"))
    )
    (net (code "18") (name "IF_SWDIO") (class "Default")
      (node (ref "IC3") (pin "25") (pinfunction "SWDIO/PIO0_15/AD4/CT32B1_MAT2_25") (pintype "bidirectional"))
    )
    (net (code "19") (name "LED_COM_GREEN") (class "Default")
      (node (ref "IC3") (pin "21") (pinfunction "TDI/PIO0_11/AD0/CT32B0_MAT3_21") (pintype "bidirectional"))
      (node (ref "LED2") (pin "C") (pinfunction "C_C") (pintype "passive"))
    )
    (net (code "20") (name "LED_DAP_BLUE") (class "Default")
      (node (ref "IC3") (pin "12") (pinfunction "PIO0_21/CT16B1_MAT0_12") (pintype "bidirectional"))
      (node (ref "LED1") (pin "C") (pinfunction "C_C") (pintype "passive"))
    )
    (net (code "21") (name "LED_PWR_RED") (class "Default")
      (node (ref "IC3") (pin "7") (pinfunction "PIO0_20/CT16B1_CAP0_7") (pintype "bidirectional"))
      (node (ref "LED3") (pin "A") (pinfunction "A_A") (pintype "passive"))
    )
    (net (code "22") (name "MISO1") (class "Default")
      (node (ref "CON1") (pin "2") (pinfunction "MISO_2") (pintype "bidirectional"))
      (node (ref "CON10") (pin "7") (pinfunction "MISO_7") (pintype "bidirectional"))
      (node (ref "SKT1") (pin "14") (pinfunction "MISO1_14") (pintype "bidirectional"))
      (node (ref "SKT1") (pin "P$54") (pinfunction "P$54_P$54") (pintype "bidirectional"))
    )
    (net (code "23") (name "MISO2") (class "Default")
      (node (ref "CON7") (pin "2") (pinfunction "MISO_2") (pintype "bidirectional"))
      (node (ref "SKT1") (pin "27") (pinfunction "MISO2_27") (pintype "bidirectional"))
      (node (ref "SKT1") (pin "P$67") (pinfunction "P$67_P$67") (pintype "bidirectional"))
    )
    (net (code "24") (name "MOSI1") (class "Default")
      (node (ref "CON1") (pin "3") (pinfunction "MOSI_3") (pintype "bidirectional"))
      (node (ref "CON10") (pin "3") (pinfunction "MOSI_3") (pintype "bidirectional"))
      (node (ref "LCD1") (pin "P$13") (pinfunction "SDA_P$13") (pintype "bidirectional"))
      (node (ref "SKT1") (pin "13") (pinfunction "MOSI1_13") (pintype "bidirectional"))
      (node (ref "SKT1") (pin "P$53") (pinfunction "P$53_P$53") (pintype "bidirectional"))
    )
    (net (code "25") (name "MOSI2") (class "Default")
      (node (ref "CON7") (pin "3") (pinfunction "MOSI_3") (pintype "bidirectional"))
      (node (ref "SKT1") (pin "28") (pinfunction "MOSI2_28") (pintype "bidirectional"))
      (node (ref "SKT1") (pin "P$68") (pinfunction "P$68_P$68") (pintype "bidirectional"))
    )
    (net (code "26") (name "Net-(C6-P$1)") (class "Default")
      (node (ref "C6") (pin "1") (pinfunction "P$1_1") (pintype "passive"))
      (node (ref "IC3") (pin "5") (pinfunction "XTALOUT_5") (pintype "output"))
      (node (ref "Q1") (pin "P$1") (pinfunction "1_P$1") (pintype "passive"))
    )
    (net (code "27") (name "Net-(C7-P$1)") (class "Default")
      (node (ref "C7") (pin "1") (pinfunction "P$1_1") (pintype "passive"))
      (node (ref "IC3") (pin "4") (pinfunction "XTALIN_4") (pintype "input"))
      (node (ref "Q1") (pin "P$3") (pinfunction "2_P$3") (pintype "passive"))
    )
    (net (code "28") (name "Net-(C8-P$1)") (class "Default")
      (node (ref "C8") (pin "1") (pinfunction "P$1_1") (pintype "passive"))
      (node (ref "IC3") (pin "13") (pinfunction "USB_DM_13") (pintype "bidirectional"))
      (node (ref "R9") (pin "2") (pinfunction "P$2_2") (pintype "passive"))
    )
    (net (code "29") (name "Net-(C9-P$1)") (class "Default")
      (node (ref "C9") (pin "1") (pinfunction "P$1_1") (pintype "passive"))
      (node (ref "IC3") (pin "14") (pinfunction "USB_DP_14") (pintype "bidirectional"))
      (node (ref "R10") (pin "2") (pinfunction "P$2_2") (pintype "passive"))
      (node (ref "R8") (pin "2") (pinfunction "P$2_2") (pintype "passive"))
    )
    (net (code "30") (name "Net-(C11-P$1)") (class "Default")
      (node (ref "C11") (pin "1") (pinfunction "P$1_1") (pintype "passive"))
      (node (ref "LCD1") (pin "P$1") (pinfunction "V0_P$1") (pintype "bidirectional"))
    )
    (net (code "31") (name "Net-(C12-P$1)") (class "Default")
      (node (ref "C12") (pin "1") (pinfunction "P$1_1") (pintype "passive"))
      (node (ref "LCD1") (pin "P$2") (pinfunction "V1_P$2") (pintype "bidirectional"))
    )
    (net (code "32") (name "Net-(C13-P$1)") (class "Default")
      (node (ref "C13") (pin "1") (pinfunction "P$1_1") (pintype "passive"))
      (node (ref "LCD1") (pin "P$3") (pinfunction "V2_P$3") (pintype "bidirectional"))
    )
    (net (code "33") (name "Net-(C14-P$1)") (class "Default")
      (node (ref "C14") (pin "1") (pinfunction "P$1_1") (pintype "passive"))
      (node (ref "LCD1") (pin "P$4") (pinfunction "V3_P$4") (pintype "bidirectional"))
    )
    (net (code "34") (name "Net-(C15-P$1)") (class "Default")
      (node (ref "C15") (pin "1") (pinfunction "P$1_1") (pintype "passive"))
      (node (ref "LCD1") (pin "P$5") (pinfunction "V4_P$5") (pintype "bidirectional"))
    )
    (net (code "35") (name "Net-(C16-P$1)") (class "Default")
      (node (ref "C16") (pin "1") (pinfunction "P$1_1") (pintype "passive"))
      (node (ref "LCD1") (pin "P$9") (pinfunction "C1-_P$9") (pintype "bidirectional"))
    )
    (net (code "36") (name "Net-(C16-P$2)") (class "Default")
      (node (ref "C16") (pin "2") (pinfunction "P$2_2") (pintype "passive"))
      (node (ref "LCD1") (pin "P$8") (pinfunction "C1+_P$8") (pintype "bidirectional"))
    )
    (net (code "37") (name "Net-(C17-P$1)") (class "Default")
      (node (ref "C17") (pin "1") (pinfunction "P$1_1") (pintype "passive"))
      (node (ref "LCD1") (pin "P$7") (pinfunction "C2+_P$7") (pintype "bidirectional"))
    )
    (net (code "38") (name "Net-(C17-P$2)") (class "Default")
      (node (ref "C17") (pin "2") (pinfunction "P$2_2") (pintype "passive"))
      (node (ref "LCD1") (pin "P$6") (pinfunction "C2-_P$6") (pintype "bidirectional"))
    )
    (net (code "39") (name "Net-(C18-P$1)") (class "Default")
      (node (ref "C18") (pin "1") (pinfunction "P$1_1") (pintype "passive"))
      (node (ref "LCD1") (pin "P$10") (pinfunction "VOUT_P$10") (pintype "bidirectional"))
    )
    (net (code "40") (name "Net-(CON9-PadD+)") (class "Default")
      (node (ref "CON9") (pin "D+") (pinfunction "D+_D+") (pintype "bidirectional"))
      (node (ref "IC1") (pin "1") (pinfunction "IO1_1") (pintype "bidirectional"))
    )
    (net (code "41") (name "Net-(CON9-PadD-)") (class "Default")
      (node (ref "CON9") (pin "D-") (pinfunction "D-_D-") (pintype "bidirectional"))
      (node (ref "IC1") (pin "3") (pinfunction "IO2_3") (pintype "bidirectional"))
    )
    (net (code "42") (name "Net-(IC1-VBUS)") (class "Default")
      (node (ref "CON9") (pin "VBUS") (pinfunction "VBUS_VBUS") (pintype "bidirectional"))
      (node (ref "IC1") (pin "5") (pinfunction "VBUS_5") (pintype "bidirectional"))
      (node (ref "SW3") (pin "2") (pinfunction "2_2") (pintype "bidirectional"))
    )
    (net (code "43") (name "Net-(IC3-PIO0_3{slash}USB_VBUS)") (class "Default")
      (node (ref "IC3") (pin "9") (pinfunction "PIO0_3/USB_VBUS_9") (pintype "bidirectional"))
      (node (ref "R4") (pin "1") (pinfunction "P$1_1") (pintype "passive"))
    )
    (net (code "44") (name "Net-(R1-P$2)") (class "Default")
      (node (ref "LED1") (pin "A") (pinfunction "A_A") (pintype "passive"))
      (node (ref "R1") (pin "2") (pinfunction "P$2_2") (pintype "passive"))
    )
    (net (code "45") (name "Net-(R2-P$2)") (class "Default")
      (node (ref "LED2") (pin "A") (pinfunction "A_A") (pintype "passive"))
      (node (ref "R2") (pin "2") (pinfunction "P$2_2") (pintype "passive"))
    )
    (net (code "46") (name "Net-(R3-P$2)") (class "Default")
      (node (ref "LED3") (pin "C") (pinfunction "C_C") (pintype "passive"))
      (node (ref "R3") (pin "2") (pinfunction "P$2_2") (pintype "passive"))
    )
    (net (code "47") (name "Net-(R8-P$1)") (class "Default")
      (node (ref "R8") (pin "1") (pinfunction "P$1_1") (pintype "passive"))
      (node (ref "T1") (pin "3") (pinfunction "D_3") (pintype "passive"))
    )
    (net (code "48") (name "Net-(R11-P$2)") (class "Default")
      (node (ref "LED4") (pin "C") (pinfunction "C_C") (pintype "passive"))
      (node (ref "R11") (pin "2") (pinfunction "P$2_2") (pintype "passive"))
    )
    (net (code "49") (name "Net-(R12-P$2)") (class "Default")
      (node (ref "LED5") (pin "C") (pinfunction "C_C") (pintype "passive"))
      (node (ref "R12") (pin "2") (pinfunction "P$2_2") (pintype "passive"))
    )
    (net (code "50") (name "Net-(R13-P$2)") (class "Default")
      (node (ref "LED6") (pin "C") (pinfunction "C_C") (pintype "passive"))
      (node (ref "R13") (pin "2") (pinfunction "P$2_2") (pintype "passive"))
    )
    (net (code "51") (name "Net-(R17-P$2)") (class "Default")
      (node (ref "LCD1") (pin "A") (pinfunction "A_A") (pintype "bidirectional"))
      (node (ref "R17") (pin "2") (pinfunction "P$2_2") (pintype "passive"))
    )
    (net (code "52") (name "Net-(R19-P$2)") (class "Default")
      (node (ref "R19") (pin "2") (pinfunction "P$2_2") (pintype "passive"))
      (node (ref "R20") (pin "2") (pinfunction "P$2_2") (pintype "passive"))
      (node (ref "R21") (pin "2") (pinfunction "P$2_2") (pintype "passive"))
      (node (ref "TP3") (pin "TP") (pinfunction "TP_TP") (pintype "input"))
    )
    (net (code "53") (name "Net-(R22-P$1)") (class "Default")
      (node (ref "R22") (pin "1") (pinfunction "P$1_1") (pintype "passive"))
      (node (ref "VR1") (pin "P$2") (pinfunction "S_P$2") (pintype "passive"))
    )
    (net (code "54") (name "PWM0") (class "Default")
      (node (ref "R11") (pin "1") (pinfunction "P$1_1") (pintype "passive"))
      (node (ref "SKT1") (pin "21") (pinfunction "PWM0_21") (pintype "bidirectional"))
      (node (ref "SKT1") (pin "P$61") (pinfunction "P$61_P$61") (pintype "bidirectional"))
    )
    (net (code "55") (name "PWM1") (class "Default")
      (node (ref "R12") (pin "1") (pinfunction "P$1_1") (pintype "passive"))
      (node (ref "SKT1") (pin "22") (pinfunction "PWM1_22") (pintype "bidirectional"))
      (node (ref "SKT1") (pin "P$62") (pinfunction "P$62_P$62") (pintype "bidirectional"))
    )
    (net (code "56") (name "PWM2") (class "Default")
      (node (ref "R13") (pin "1") (pinfunction "P$1_1") (pintype "passive"))
      (node (ref "SKT1") (pin "23") (pinfunction "PWM2_23") (pintype "bidirectional"))
      (node (ref "SKT1") (pin "P$63") (pinfunction "P$63_P$63") (pintype "bidirectional"))
    )
    (net (code "57") (name "RX1") (class "Default")
      (node (ref "CON2") (pin "1") (pinfunction "RX/SCL_1") (pintype "bidirectional"))
      (node (ref "R23") (pin "2") (pinfunction "P$2_2") (pintype "passive"))
      (node (ref "SKT1") (pin "10") (pinfunction "RX1_10") (pintype "bidirectional"))
      (node (ref "SKT1") (pin "P$50") (pinfunction "P$50_P$50") (pintype "bidirectional"))
    )
    (net (code "58") (name "RX2") (class "Default")
      (node (ref "CON6") (pin "1") (pinfunction "RX/SCL_1") (pintype "bidirectional"))
      (node (ref "R18") (pin "2") (pinfunction "P$2_2") (pintype "passive"))
      (node (ref "SKT1") (pin "31") (pinfunction "RX2_31") (pintype "bidirectional"))
      (node (ref "SKT1") (pin "P$71") (pinfunction "P$71_P$71") (pintype "bidirectional"))
    )
    (net (code "59") (name "SCK1") (class "Default")
      (node (ref "CON1") (pin "1") (pinfunction "SCK_1") (pintype "bidirectional"))
      (node (ref "CON10") (pin "5") (pinfunction "SCK_5") (pintype "bidirectional"))
      (node (ref "LCD1") (pin "P$14") (pinfunction "SCL_P$14") (pintype "bidirectional"))
      (node (ref "SKT1") (pin "15") (pinfunction "SCK1_15") (pintype "bidirectional"))
      (node (ref "SKT1") (pin "P$55") (pinfunction "P$55_P$55") (pintype "bidirectional"))
    )
    (net (code "60") (name "SCK2") (class "Default")
      (node (ref "CON7") (pin "1") (pinfunction "SCK_1") (pintype "bidirectional"))
      (node (ref "SKT1") (pin "26") (pinfunction "SCK2_26") (pintype "bidirectional"))
      (node (ref "SKT1") (pin "P$66") (pinfunction "P$66_P$66") (pintype "bidirectional"))
    )
    (net (code "61") (name "SCL") (class "Default")
      (node (ref "IC4") (pin "2") (pinfunction "SCL_2") (pintype "bidirectional"))
      (node (ref "IC5") (pin "6") (pinfunction "SCL_6") (pintype "bidirectional"))
      (node (ref "R15") (pin "1") (pinfunction "P$1_1") (pintype "passive"))
      (node (ref "SJ1") (pin "2") (pinfunction "2_2") (pintype "passive"))
    )
    (net (code "62") (name "SCL1") (class "Default")
      (node (ref "CON5") (pin "1") (pinfunction "RX/SCL_1") (pintype "bidirectional"))
      (node (ref "SJ1") (pin "1") (pinfunction "1_1") (pintype "passive"))
      (node (ref "SKT1") (pin "12") (pinfunction "SCL1_12") (pintype "bidirectional"))
      (node (ref "SKT1") (pin "P$52") (pinfunction "P$52_P$52") (pintype "bidirectional"))
    )
    (net (code "63") (name "SCL2") (class "Default")
      (node (ref "CON8") (pin "1") (pinfunction "RX/SCL_1") (pintype "bidirectional"))
      (node (ref "SJ1") (pin "3") (pinfunction "3_3") (pintype "passive"))
      (node (ref "SKT1") (pin "29") (pinfunction "SCL2_29") (pintype "bidirectional"))
      (node (ref "SKT1") (pin "P$69") (pinfunction "P$69_P$69") (pintype "bidirectional"))
    )
    (net (code "64") (name "SDA") (class "Default")
      (node (ref "IC4") (pin "1") (pinfunction "SDA_1") (pintype "bidirectional"))
      (node (ref "IC5") (pin "5") (pinfunction "SDA_5") (pintype "bidirectional"))
      (node (ref "R14") (pin "1") (pinfunction "P$1_1") (pintype "passive"))
      (node (ref "SJ2") (pin "2") (pinfunction "2_2") (pintype "passive"))
    )
    (net (code "65") (name "SDA1") (class "Default")
      (node (ref "CON5") (pin "2") (pinfunction "TX/SDA_2") (pintype "bidirectional"))
      (node (ref "SJ2") (pin "1") (pinfunction "1_1") (pintype "passive"))
      (node (ref "SKT1") (pin "11") (pinfunction "SDA1_11") (pintype "bidirectional"))
      (node (ref "SKT1") (pin "P$51") (pinfunction "P$51_P$51") (pintype "bidirectional"))
    )
    (net (code "66") (name "SDA2") (class "Default")
      (node (ref "CON8") (pin "2") (pinfunction "TX/SDA_2") (pintype "bidirectional"))
      (node (ref "SJ2") (pin "3") (pinfunction "3_3") (pintype "passive"))
      (node (ref "SKT1") (pin "30") (pinfunction "SDA2_30") (pintype "bidirectional"))
      (node (ref "SKT1") (pin "P$70") (pinfunction "P$70_P$70") (pintype "bidirectional"))
    )
    (net (code "67") (name "TGT_CTS") (class "Default")
      (node (ref "IC3") (pin "30") (pinfunction "PIO0_17/~{RTS}/CT32B0_CAP0/SCLK_30") (pintype "bidirectional"))
      (node (ref "SKT1") (pin "39") (pinfunction "TGT_CTS_39") (pintype "bidirectional"))
      (node (ref "SKT1") (pin "P$79") (pinfunction "P$79_P$79") (pintype "bidirectional"))
    )
    (net (code "68") (name "TGT_NRESET") (class "Default")
      (node (ref "CON11") (pin "10") (pinfunction "NRESET_10") (pintype "bidirectional"))
      (node (ref "D1") (pin "A") (pinfunction "A_A") (pintype "passive"))
      (node (ref "IC3") (pin "8") (pinfunction "PIO0_2/SSEL0/CT16B0_CAP0_8") (pintype "bidirectional"))
      (node (ref "SKT1") (pin "6") (pinfunction "NRESET_6") (pintype "bidirectional"))
      (node (ref "SKT1") (pin "P$46") (pinfunction "P$46_P$46") (pintype "bidirectional"))
    )
    (net (code "69") (name "TGT_NRESET_BUTTON") (class "Default")
      (node (ref "D1") (pin "K") (pinfunction "K_K") (pintype "passive"))
      (node (ref "R6") (pin "2") (pinfunction "P$2_2") (pintype "passive"))
      (node (ref "R7") (pin "2") (pinfunction "P$2_2") (pintype "passive"))
      (node (ref "SW1") (pin "A1") (pinfunction "A1_A1") (pintype "passive"))
      (node (ref "SW1") (pin "A2") (pinfunction "A2_A2") (pintype "passive"))
    )
    (net (code "70") (name "TGT_NRESET_FB") (class "Default")
      (node (ref "IC3") (pin "3") (pinfunction "PIO0_1/CLKOUT/CT32B0_MAT2/USB_FTOGGLE_3") (pintype "bidirectional"))
      (node (ref "R6") (pin "1") (pinfunction "P$1_1") (pintype "passive"))
    )
    (net (code "71") (name "TGT_NRESET_FB_ISP") (class "Default")
      (node (ref "IC3") (pin "1") (pinfunction "PIO1_19/~{DTR}/SSEL1_1") (pintype "bidirectional"))
      (node (ref "R7") (pin "1") (pinfunction "P$1_1") (pintype "passive"))
    )
    (net (code "72") (name "TGT_RTS") (class "Default")
      (node (ref "IC3") (pin "16") (pinfunction "PIO0_7/~{CTS}_16") (pintype "bidirectional"))
      (node (ref "JP2") (pin "2") (pinfunction "2_2") (pintype "passive"))
      (node (ref "SKT1") (pin "38") (pinfunction "TGT_RTS_38") (pintype "bidirectional"))
      (node (ref "SKT1") (pin "P$78") (pinfunction "P$78_P$78") (pintype "bidirectional"))
    )
    (net (code "73") (name "TGT_RX") (class "Default")
      (node (ref "CON11") (pin "8") (pinfunction "TGT_RX_8") (pintype "bidirectional"))
      (node (ref "IC3") (pin "32") (pinfunction "PIO0_19/TXD/CT32B0_MAT1_32") (pintype "bidirectional"))
      (node (ref "SKT1") (pin "8") (pinfunction "TGT_RX_8") (pintype "bidirectional"))
      (node (ref "SKT1") (pin "P$48") (pinfunction "P$48_P$48") (pintype "bidirectional"))
    )
    (net (code "74") (name "TGT_SWCLK") (class "Default")
      (node (ref "CON11") (pin "4") (pinfunction "SWCLK_4") (pintype "bidirectional"))
      (node (ref "IC3") (pin "18") (pinfunction "PIO0_9/MOSI0/CT16B0_MAT1_18") (pintype "bidirectional"))
      (node (ref "JP2") (pin "1") (pinfunction "1_1") (pintype "passive"))
      (node (ref "SKT1") (pin "5") (pinfunction "SWCLK_5") (pintype "bidirectional"))
      (node (ref "SKT1") (pin "P$45") (pinfunction "P$45_P$45") (pintype "bidirectional"))
    )
    (net (code "75") (name "TGT_SWDIO") (class "Default")
      (node (ref "CON11") (pin "2") (pinfunction "SWDIO_2") (pintype "bidirectional"))
      (node (ref "IC3") (pin "17") (pinfunction "PIO0_8/MISO0/CT16B0_MAT0_17") (pintype "bidirectional"))
      (node (ref "SKT1") (pin "4") (pinfunction "SWDIO_4") (pintype "bidirectional"))
      (node (ref "SKT1") (pin "P$44") (pinfunction "P$44_P$44") (pintype "bidirectional"))
    )
    (net (code "76") (name "TGT_TX") (class "Default")
      (node (ref "CON11") (pin "7") (pinfunction "TGT_TX_7") (pintype "bidirectional"))
      (node (ref "IC3") (pin "31") (pinfunction "PIO0_18/RXD/CT32B0_MAT0_31") (pintype "bidirectional"))
      (node (ref "SKT1") (pin "7") (pinfunction "TGT_TX_7") (pintype "bidirectional"))
      (node (ref "SKT1") (pin "P$47") (pinfunction "P$47_P$47") (pintype "bidirectional"))
    )
    (net (code "77") (name "TX1") (class "Default")
      (node (ref "CON2") (pin "2") (pinfunction "TX/SDA_2") (pintype "bidirectional"))
      (node (ref "R23") (pin "1") (pinfunction "P$1_1") (pintype "passive"))
      (node (ref "SKT1") (pin "9") (pinfunction "TX1_9") (pintype "bidirectional"))
      (node (ref "SKT1") (pin "P$49") (pinfunction "P$49_P$49") (pintype "bidirectional"))
    )
    (net (code "78") (name "TX2") (class "Default")
      (node (ref "CON6") (pin "2") (pinfunction "TX/SDA_2") (pintype "bidirectional"))
      (node (ref "R18") (pin "1") (pinfunction "P$1_1") (pintype "passive"))
      (node (ref "SKT1") (pin "32") (pinfunction "TX2_32") (pintype "bidirectional"))
      (node (ref "SKT1") (pin "P$72") (pinfunction "P$72_P$72") (pintype "bidirectional"))
    )
    (net (code "79") (name "USB-D+") (class "Default")
      (node (ref "IC1") (pin "6") (pinfunction "IO1_6") (pintype "bidirectional"))
      (node (ref "R10") (pin "1") (pinfunction "P$1_1") (pintype "passive"))
    )
    (net (code "80") (name "USB-D-") (class "Default")
      (node (ref "IC1") (pin "4") (pinfunction "IO2_4") (pintype "bidirectional"))
      (node (ref "R9") (pin "1") (pinfunction "P$1_1") (pintype "passive"))
    )
    (net (code "81") (name "USB-SCON") (class "Default")
      (node (ref "IC3") (pin "15") (pinfunction "PIO0_6/~{USB_CONNECT}/SCK0_15") (pintype "bidirectional"))
      (node (ref "T1") (pin "1") (pinfunction "G_1") (pintype "passive"))
    )
    (net (code "82") (name "VCC_GROVE") (class "Default")
      (node (ref "CON2") (pin "3") (pinfunction "VCC_3") (pintype "bidirectional"))
      (node (ref "CON3") (pin "3") (pinfunction "VCC_3") (pintype "bidirectional"))
      (node (ref "CON4") (pin "3") (pinfunction "VCC_3") (pintype "bidirectional"))
      (node (ref "CON5") (pin "3") (pinfunction "VCC_3") (pintype "bidirectional"))
      (node (ref "CON6") (pin "3") (pinfunction "VCC_3") (pintype "bidirectional"))
      (node (ref "CON8") (pin "3") (pinfunction "VCC_3") (pintype "bidirectional"))
      (node (ref "JP1") (pin "2") (pinfunction "2_2") (pintype "passive"))
    )
    (net (code "83") (name "unconnected-(CON10-NC-Pad1)") (class "Default")
      (node (ref "CON10") (pin "1") (pinfunction "NC_1") (pintype "bidirectional"))
    )
    (net (code "84") (name "unconnected-(CON10-NC-Pad8)") (class "Default")
      (node (ref "CON10") (pin "8") (pinfunction "NC_8") (pintype "bidirectional"))
    )
    (net (code "85") (name "unconnected-(CON10-PadCD)") (class "Default")
      (node (ref "CON10") (pin "CD") (pinfunction "CD_CD") (pintype "bidirectional"))
    )
    (net (code "86") (name "unconnected-(CON11-SWO-Pad6)") (class "Default")
      (node (ref "CON11") (pin "6") (pinfunction "SWO_6") (pintype "bidirectional"))
    )
    (net (code "87") (name "unconnected-(CON11-VCC-Pad1)") (class "Default")
      (node (ref "CON11") (pin "1") (pinfunction "VCC_1") (pintype "bidirectional"))
    )
    (net (code "88") (name "unconnected-(IC3-PIO0_4{slash}SCL-Pad10)") (class "Default")
      (node (ref "IC3") (pin "10") (pinfunction "PIO0_4/SCL_10") (pintype "bidirectional"))
    )
    (net (code "89") (name "unconnected-(IC3-PIO0_5{slash}SDA-Pad11)") (class "Default")
      (node (ref "IC3") (pin "11") (pinfunction "PIO0_5/SDA_11") (pintype "bidirectional"))
    )
    (net (code "90") (name "unconnected-(IC3-PIO0_16{slash}AD5{slash}CT32B1_MAT3{slash}WAKEUP-Pad26)") (class "Default")
      (node (ref "IC3") (pin "26") (pinfunction "PIO0_16/AD5/CT32B1_MAT3/WAKEUP_26") (pintype "bidirectional"))
    )
    (net (code "91") (name "unconnected-(IC3-PIO0_22{slash}AD6{slash}CT16B1_MAT1{slash}MISO1-Pad20)") (class "Default")
      (node (ref "IC3") (pin "20") (pinfunction "PIO0_22/AD6/CT16B1_MAT1/MISO1_20") (pintype "bidirectional"))
    )
    (net (code "92") (name "unconnected-(IC3-PIO0_23{slash}AD7-Pad27)") (class "Default")
      (node (ref "IC3") (pin "27") (pinfunction "PIO0_23/AD7_27") (pintype "bidirectional"))
    )
    (net (code "93") (name "unconnected-(IC3-PIO1_15{slash}~{DCD}{slash}CT16B0_MAT2{slash}SCK1-Pad28)") (class "Default")
      (node (ref "IC3") (pin "28") (pinfunction "PIO1_15/~{DCD}/CT16B0_MAT2/SCK1_28") (pintype "bidirectional"))
    )
    (net (code "94") (name "unconnected-(IC3-TDO{slash}PIO0_13{slash}AD2{slash}CT32B1_MAT0-Pad23)") (class "Default")
      (node (ref "IC3") (pin "23") (pinfunction "TDO/PIO0_13/AD2/CT32B1_MAT0_23") (pintype "bidirectional"))
    )
    (net (code "95") (name "unconnected-(IC3-TMS{slash}PIO0_12{slash}AD1{slash}CT32B1_CAP0-Pad22)") (class "Default")
      (node (ref "IC3") (pin "22") (pinfunction "TMS/PIO0_12/AD1/CT32B1_CAP0_22") (pintype "bidirectional"))
    )
    (net (code "96") (name "unconnected-(IC3-~{TRST}{slash}PIO0_14{slash}AD3{slash}CT32B1_MAT1-Pad24)") (class "Default")
      (node (ref "IC3") (pin "24") (pinfunction "~{TRST}/PIO0_14/AD3/CT32B1_MAT1_24") (pintype "bidirectional"))
    )
    (net (code "97") (name "unconnected-(IC4-OS-Pad3)") (class "Default")
      (node (ref "IC4") (pin "3") (pinfunction "OS_3") (pintype "bidirectional"))
    )
    (net (code "98") (name "unconnected-(IC5-WP-Pad7)") (class "Default")
      (node (ref "IC5") (pin "7") (pinfunction "WP_7") (pintype "bidirectional"))
    )
    (net (code "99") (name "unconnected-(SW3-Pad1)") (class "Default")
      (node (ref "SW3") (pin "1") (pinfunction "1_1") (pintype "bidirectional"))
    )
    (net (code "100") (name "unconnected-(SW3-Pad5)") (class "Default")
      (node (ref "SW3") (pin "5") (pinfunction "5_5") (pintype "bidirectional"))
    )
    (net (code "101") (name "unconnected-(SW3-Pad6)") (class "Default")
      (node (ref "SW3") (pin "6") (pinfunction "6_6") (pintype "bidirectional"))
    )
    (net (code "102") (name "unconnected-(SW3-Pad7)") (class "Default")
      (node (ref "SW3") (pin "7") (pinfunction "7_7") (pintype "bidirectional"))
    )
  )
)
